# LiBattery-ChargeAndDischarge.net
KiCad netlist of a schematic drawn in Altium Designer
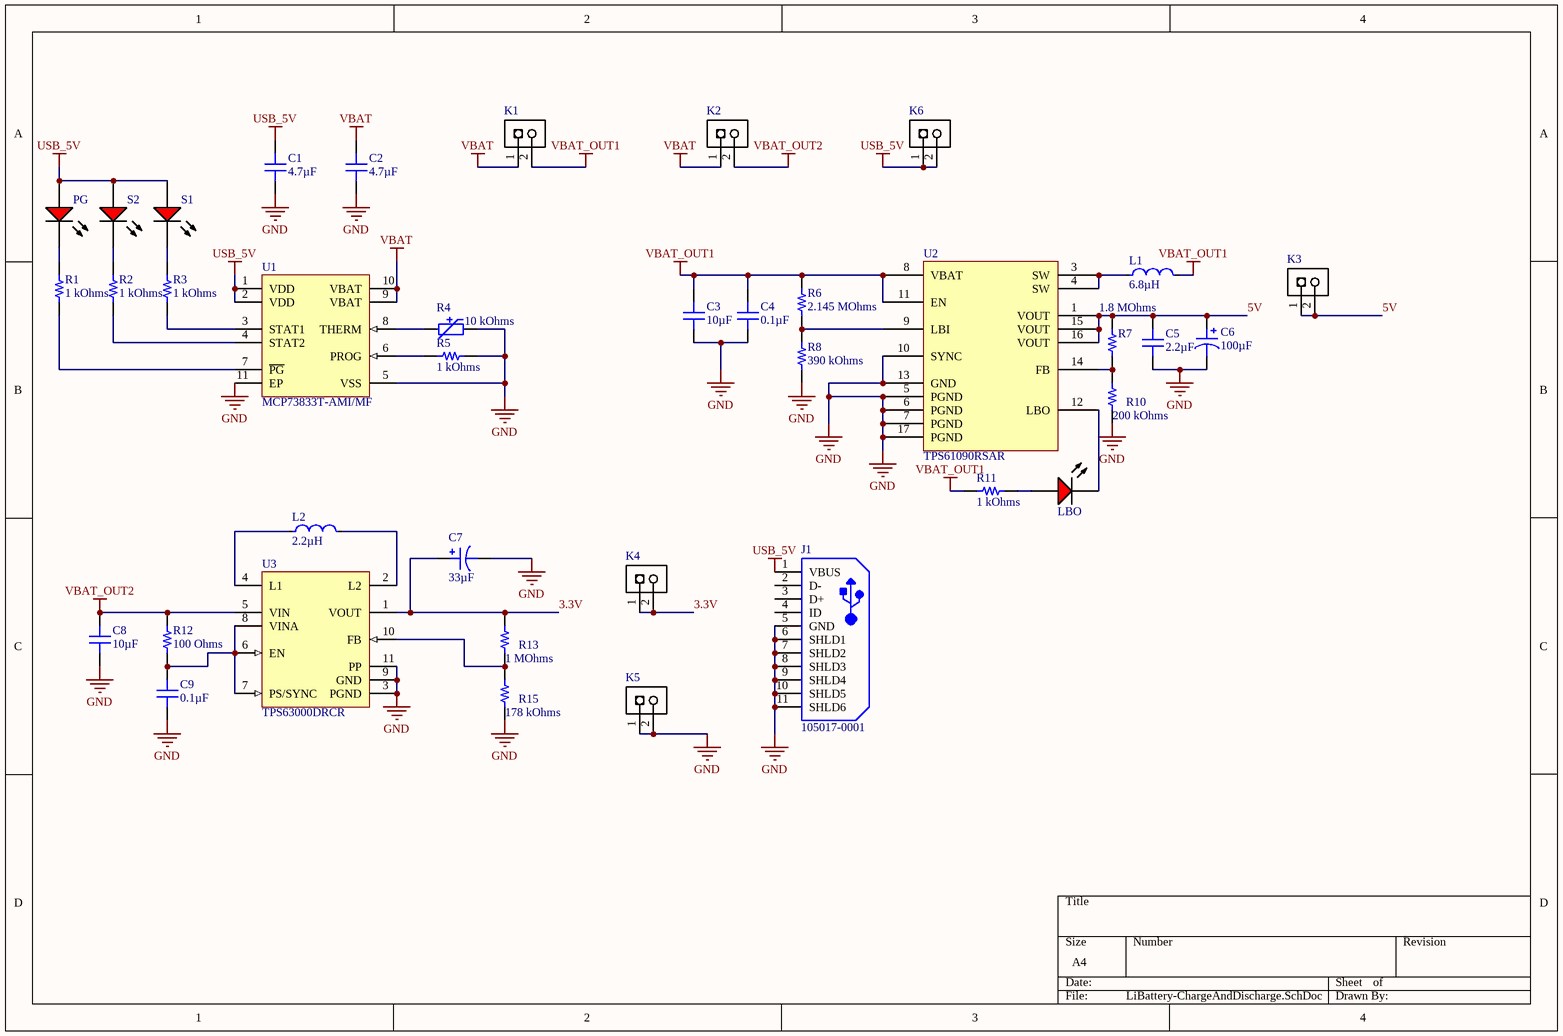
[diagram p0: LiBattery-ChargeAndDischarge.SchDoc]

(export (version "E")
  (design (tool "Eeschema 10.0.6"))
  (components
    (comp (ref "C1")
      (value "4.7µF")
      (footprint "CAP 0603_1608")
      (description "CAP CER 0603 1UF 16V X7R 10%")
      (fields (field (name "PART NUMBER") "C0603C105K4RACAUTO") (field (name "MANUFACTURER") "KEMET"))
      (libsource (lib "Celestial Altium Library - altium_library") (part "Capacitor"))
    )
    (comp (ref "C2")
      (value "4.7µF")
      (footprint "CAP 0603_1608")
      (description "CAP CER 0603 1UF 16V X7R 10%")
      (fields (field (name "PART NUMBER") "C0603C105K4RACAUTO") (field (name "MANUFACTURER") "KEMET"))
      (libsource (lib "Celestial Altium Library - altium_library") (part "Capacitor"))
    )
    (comp (ref "C3")
      (value "10µF")
      (footprint "CAP 0603_1608")
      (description "CAP CER 10UF 6.3V X5R 0603")
      (fields
        (field (name "PART NUMBER") "GRM188R60J106ME47D")
        (field (name "MANUFACTURER") "Murata Electronics")
      )
      (libsource (lib "Celestial Altium Library - altium_library") (part "Capacitor"))
    )
    (comp (ref "C4")
      (value "0.1µF")
      (footprint "CAP 0603_1608")
      (description "CAP CER 0.1UF 10V X7R 0603")
      (fields
        (field (name "PART NUMBER") "100X14W104MV4T")
        (field (name "MANUFACTURER") "Johanson Dielectrics Inc.")
      )
      (libsource (lib "Celestial Altium Library - altium_library") (part "Capacitor"))
    )
    (comp (ref "C5")
      (value "2.2µF")
      (footprint "CAP 0603_1608")
      (description "CAP CER 2.2UF 16V Y5V 0603")
      (fields (field (name "PART NUMBER") "CC0603ZRY5V7BB225") (field (name "MANUFACTURER") "Yageo"))
      (libsource (lib "Celestial Altium Library - altium_library") (part "Capacitor"))
    )
    (comp (ref "C6")
      (value "100µF")
      (footprint "CAP POL 1411_3528")
      (description "CAP TANT 1UF 10% 35V 1411")
      (fields (field (name "PART NUMBER") "CWR11MH105KB") (field (name "MANUFACTURER") "KEMET"))
      (libsource (lib "") (part "Polarised Capacitor_1"))
    )
    (comp (ref "C7")
      (value "33µF")
      (footprint "CAP POL 1411_3528")
      (description "CAP TANT 1UF 10% 35V 1411")
      (fields (field (name "PART NUMBER") "CWR11MH105KB") (field (name "MANUFACTURER") "KEMET"))
      (libsource (lib "Celestial Altium Library - altium_library") (part "Polarised Capacitor"))
    )
    (comp (ref "C8")
      (value "10µF")
      (footprint "CAP 0603_1608")
      (description "CAP CER 10UF 6.3V X5R 0603")
      (fields
        (field (name "PART NUMBER") "GRM188R60J106ME47D")
        (field (name "MANUFACTURER") "Murata Electronics")
      )
      (libsource (lib "Celestial Altium Library - altium_library") (part "Capacitor"))
    )
    (comp (ref "C9")
      (value "0.1µF")
      (footprint "CAP 0603_1608")
      (description "CAP CER 10UF 6.3V X5R 0603")
      (fields
        (field (name "PART NUMBER") "GRM188R60J106ME47D")
        (field (name "MANUFACTURER") "Murata Electronics")
      )
      (libsource (lib "Celestial Altium Library - altium_library") (part "Capacitor"))
    )
    (comp (ref "J1")
      (value "105017-0001")
      (footprint "USB-MICRO-B_V")
      (fields (field (name "MANUFACTURER") "Molex"))
      (libsource (lib "Altium Content Vault") (part "USB-5-6SHLD"))
    )
    (comp (ref "K1")
      (value "HEADER-1X2")
      (footprint "HEADER-1X2")
      (libsource (lib "vh_altium_library") (part "HEADER-1X2"))
    )
    (comp (ref "K2")
      (value "HEADER-1X2")
      (footprint "HEADER-1X2")
      (libsource (lib "vh_altium_library") (part "HEADER-1X2"))
    )
    (comp (ref "K3")
      (value "HEADER-1X2")
      (footprint "HEADER-1X2")
      (libsource (lib "vh_altium_library") (part "HEADER-1X2"))
    )
    (comp (ref "K4")
      (value "HEADER-1X2")
      (footprint "HEADER-1X2")
      (libsource (lib "vh_altium_library") (part "HEADER-1X2"))
    )
    (comp (ref "K5")
      (value "HEADER-1X2")
      (footprint "HEADER-1X2")
      (libsource (lib "vh_altium_library") (part "HEADER-1X2"))
    )
    (comp (ref "K6")
      (value "HEADER-1X2")
      (footprint "HEADER-1X2")
      (libsource (lib "vh_altium_library") (part "HEADER-1X2"))
    )
    (comp (ref "L1")
      (value "6.8µH")
      (footprint "FP-IHLP-2525CZ-FP_2_413x3-MFG")
      (description "Commercial Inductors, High Saturation Series 6.8uH 4.5A 60mΩ 20%")
      (fields (field (name "TOLERANCE") "20%"))
      (libsource (lib "Altium Content Vault") (part "725321dda6339637d4d059423bc1c3c"))
    )
    (comp (ref "L2")
      (value "2.2µH")
      (footprint "FP-IHLP-2525CZ-FP_2_413x3-MFG")
      (description "Commercial Inductors, High Saturation Series 6.8uH 4.5A 60mΩ 20%")
      (fields (field (name "TOLERANCE") "20%"))
      (libsource (lib "Altium Content Vault") (part "725321dda6339637d4d059423bc1c3c"))
    )
    (comp (ref "LBO")
      (value "TLMS1100-GS08")
      (footprint "VISH-TLMX1100_V")
      (description "LED, RED, 2.1 V, -40 to 100 degC, 2-Pin SMD (0603), RoHS, Tape and Reel")
      (fields (field (name "TOLERANCE") "5%"))
      (libsource (lib "Altium Content Vault") (part "LED-RED-AK-2"))
    )
    (comp (ref "PG")
      (value "TLMS1100-GS08")
      (footprint "VISH-TLMX1100_V")
      (description "LED, RED, 2.1 V, -40 to 100 degC, 2-Pin SMD (0603), RoHS, Tape and Reel")
      (fields (field (name "TOLERANCE") "5%"))
      (libsource (lib "Altium Content Vault") (part "LED-RED-AK-2"))
    )
    (comp (ref "R1")
      (value "1 kOhms")
      (footprint "RES 0603_1608")
      (description "RES 10K OHM 0.1% 1/16W 0603")
      (fields
        (field (name "PART NUMBER") "RNCS0603BKE10K0")
        (field (name "MANUFACTURER") "Stackpole Electronics Inc")
      )
      (libsource (lib "Celestial Altium Library - altium_library") (part "Resistor"))
    )
    (comp (ref "R2")
      (value "1 kOhms")
      (footprint "RES 0603_1608")
      (description "RES 10K OHM 0.1% 1/16W 0603")
      (fields
        (field (name "PART NUMBER") "RNCS0603BKE10K0")
        (field (name "MANUFACTURER") "Stackpole Electronics Inc")
      )
      (libsource (lib "Celestial Altium Library - altium_library") (part "Resistor"))
    )
    (comp (ref "R3")
      (value "1 kOhms")
      (footprint "RES 0603_1608")
      (description "RES 10K OHM 0.1% 1/16W 0603")
      (fields
        (field (name "PART NUMBER") "RNCS0603BKE10K0")
        (field (name "MANUFACTURER") "Stackpole Electronics Inc")
      )
      (libsource (lib "Celestial Altium Library - altium_library") (part "Resistor"))
    )
    (comp (ref "R4")
      (value "10 kOhms")
      (footprint "PTC 0603_1608")
      (description "THERMISTOR PTC 470 OHM 50% 0603")
      (fields
        (field (name "PART NUMBER") "B59641A0145A062")
        (field (name "MANUFACTURER") "TDK Electronics Inc.")
      )
      (libsource (lib "Celestial Altium Library - altium_library") (part "Thermistor PTC"))
    )
    (comp (ref "R5")
      (value "1 kOhms")
      (footprint "RES 0603_1608")
      (description "RES 10K OHM 0.1% 1/16W 0603")
      (fields
        (field (name "PART NUMBER") "RNCS0603BKE10K0")
        (field (name "MANUFACTURER") "Stackpole Electronics Inc")
      )
      (libsource (lib "Celestial Altium Library - altium_library") (part "Resistor"))
    )
    (comp (ref "R6")
      (value "2.145 MOhms")
      (footprint "RES 0603_1608")
      (description "RES 2.32M OHM 1% 1/10W 0603")
      (fields
        (field (name "PART NUMBER") "RMCF0603FT2M32")
        (field (name "MANUFACTURER") "Stackpole Electronics Inc")
      )
      (libsource (lib "Celestial Altium Library - altium_library") (part "Resistor"))
    )
    (comp (ref "R7")
      (value "1.8 MOhms")
      (footprint "RES 0603_1608")
      (description "RES 10K OHM 0.1% 1/16W 0603")
      (fields
        (field (name "PART NUMBER") "RNCS0603BKE10K0")
        (field (name "MANUFACTURER") "Stackpole Electronics Inc")
      )
      (libsource (lib "Celestial Altium Library - altium_library") (part "Resistor"))
    )
    (comp (ref "R8")
      (value "390 kOhms")
      (footprint "RES 0603_1608")
      (description "CRGP 0603 390K 1%")
      (fields
        (field (name "PART NUMBER") "CRGP0603F390K")
        (field (name "MANUFACTURER") "TE Connectivity Passive Product")
      )
      (libsource (lib "Celestial Altium Library - altium_library") (part "Resistor"))
    )
    (comp (ref "R10")
      (value "200 kOhms")
      (footprint "RES 0603_1608")
      (description "RES 10K OHM 0.1% 1/16W 0603")
      (fields
        (field (name "PART NUMBER") "RNCS0603BKE10K0")
        (field (name "MANUFACTURER") "Stackpole Electronics Inc")
      )
      (libsource (lib "Celestial Altium Library - altium_library") (part "Resistor"))
    )
    (comp (ref "R11")
      (value "1 kOhms")
      (footprint "RES 0603_1608")
      (description "RES 10K OHM 0.1% 1/16W 0603")
      (fields
        (field (name "PART NUMBER") "RNCS0603BKE10K0")
        (field (name "MANUFACTURER") "Stackpole Electronics Inc")
      )
      (libsource (lib "Celestial Altium Library - altium_library") (part "Resistor"))
    )
    (comp (ref "R12")
      (value "100 Ohms")
      (footprint "RES 0603_1608")
      (description "RES 10K OHM 0.1% 1/16W 0603")
      (fields
        (field (name "PART NUMBER") "RNCS0603BKE10K0")
        (field (name "MANUFACTURER") "Stackpole Electronics Inc")
      )
      (libsource (lib "Celestial Altium Library - altium_library") (part "Resistor"))
    )
    (comp (ref "R13")
      (value "1 MOhms")
      (footprint "RES 0603_1608")
      (description "RES 10K OHM 0.1% 1/16W 0603")
      (fields
        (field (name "PART NUMBER") "RNCS0603BKE10K0")
        (field (name "MANUFACTURER") "Stackpole Electronics Inc")
      )
      (libsource (lib "Celestial Altium Library - altium_library") (part "Resistor"))
    )
    (comp (ref "R15")
      (value "178 kOhms")
      (footprint "RES 0603_1608")
      (description "RES 10K OHM 0.1% 1/16W 0603")
      (fields
        (field (name "PART NUMBER") "RNCS0603BKE10K0")
        (field (name "MANUFACTURER") "Stackpole Electronics Inc")
      )
      (libsource (lib "Celestial Altium Library - altium_library") (part "Resistor"))
    )
    (comp (ref "S1")
      (value "TLMS1100-GS08")
      (footprint "VISH-TLMX1100_V")
      (description "LED, RED, 2.1 V, -40 to 100 degC, 2-Pin SMD (0603), RoHS, Tape and Reel")
      (fields (field (name "TOLERANCE") "5%"))
      (libsource (lib "Altium Content Vault") (part "LED-RED-AK-2"))
    )
    (comp (ref "S2")
      (value "TLMS1100-GS08")
      (footprint "VISH-TLMX1100_V")
      (description "LED, RED, 2.1 V, -40 to 100 degC, 2-Pin SMD (0603), RoHS, Tape and Reel")
      (fields (field (name "TOLERANCE") "5%"))
      (libsource (lib "Altium Content Vault") (part "LED-RED-AK-2"))
    )
    (comp (ref "U1")
      (value "MCP73833T-AMI/MF")
      (footprint "DFN-MF10")
      (libsource (lib "Altium Content Vault") (part "PM-BM-MCP73833-IL11"))
    )
    (comp (ref "U2")
      (value "TPS61090RSAR")
      (footprint "TI VQFN-16 4X4MM RSA")
      (description "IC REG BOOST ADJUSTABLE 2A 16QFN")
      (fields (field (name "MANUFACTURER") "Texas Instruments"))
      (libsource (lib "Celestial Altium Library - altium_library") (part "TI TPS61090/1/2"))
    )
    (comp (ref "U3")
      (value "TPS63000DRCR")
      (footprint "DRC0010J_V")
      (fields (field (name "MANUFACTURER") "Texas Instruments"))
      (libsource (lib "Altium Content Vault") (part "TI-TPS63000DRC10-3000X1650TP"))
    )
  )
  (nets
    (net (code "1") (name "/3.3V") (class "Default")
      (node (ref "C7") (pin "1") (pinfunction "1_1") (pintype "passive"))
      (node (ref "K4") (pin "1") (pintype "passive"))
      (node (ref "K4") (pin "2") (pintype "passive"))
      (node (ref "R13") (pin "1") (pinfunction "1_1") (pintype "passive"))
      (node (ref "U3") (pin "1") (pinfunction "VOUT_1") (pintype "power_in"))
    )
    (net (code "2") (name "/5V") (class "Default")
      (node (ref "C5") (pin "2") (pinfunction "2_2") (pintype "passive"))
      (node (ref "C6") (pin "1") (pinfunction "1_1") (pintype "passive"))
      (node (ref "K3") (pin "1") (pintype "passive"))
      (node (ref "K3") (pin "2") (pintype "passive"))
      (node (ref "R7") (pin "1") (pinfunction "1_1") (pintype "passive"))
      (node (ref "U2") (pin "1") (pinfunction "VOUT_1") (pintype "passive"))
      (node (ref "U2") (pin "15") (pinfunction "VOUT_15") (pintype "passive"))
      (node (ref "U2") (pin "16") (pinfunction "VOUT_16") (pintype "passive"))
    )
    (net (code "3") (name "GND") (class "Default")
      (node (ref "C1") (pin "1") (pinfunction "1_1") (pintype "passive"))
      (node (ref "C2") (pin "1") (pinfunction "1_1") (pintype "passive"))
      (node (ref "C3") (pin "1") (pinfunction "1_1") (pintype "passive"))
      (node (ref "C4") (pin "2") (pinfunction "2_2") (pintype "passive"))
      (node (ref "C5") (pin "1") (pinfunction "1_1") (pintype "passive"))
      (node (ref "C6") (pin "2") (pinfunction "2_2") (pintype "passive"))
      (node (ref "C7") (pin "2") (pinfunction "2_2") (pintype "passive"))
      (node (ref "C8") (pin "1") (pinfunction "1_1") (pintype "passive"))
      (node (ref "C9") (pin "2") (pinfunction "2_2") (pintype "passive"))
      (node (ref "J1") (pin "10") (pinfunction "SHLD5_10") (pintype "passive"))
      (node (ref "J1") (pin "11") (pinfunction "SHLD6_11") (pintype "passive"))
      (node (ref "J1") (pin "5") (pinfunction "GND_5") (pintype "passive"))
      (node (ref "J1") (pin "6") (pinfunction "SHLD1_6") (pintype "passive"))
      (node (ref "J1") (pin "7") (pinfunction "SHLD2_7") (pintype "passive"))
      (node (ref "J1") (pin "8") (pinfunction "SHLD3_8") (pintype "passive"))
      (node (ref "J1") (pin "9") (pinfunction "SHLD4_9") (pintype "passive"))
      (node (ref "K5") (pin "1") (pintype "passive"))
      (node (ref "K5") (pin "2") (pintype "passive"))
      (node (ref "R10") (pin "2") (pinfunction "2_2") (pintype "passive"))
      (node (ref "R15") (pin "2") (pinfunction "2_2") (pintype "passive"))
      (node (ref "R4") (pin "1") (pinfunction "1_1") (pintype "passive"))
      (node (ref "R5") (pin "1") (pinfunction "1_1") (pintype "passive"))
      (node (ref "R8") (pin "1") (pinfunction "1_1") (pintype "passive"))
      (node (ref "U1") (pin "11") (pinfunction "EP_11") (pintype "power_in"))
      (node (ref "U1") (pin "5") (pinfunction "VSS_5") (pintype "power_in"))
      (node (ref "U2") (pin "10") (pinfunction "SYNC_10") (pintype "passive"))
      (node (ref "U2") (pin "13") (pinfunction "GND_13") (pintype "passive"))
      (node (ref "U2") (pin "17") (pinfunction "PGND_17") (pintype "passive"))
      (node (ref "U2") (pin "5") (pinfunction "PGND_5") (pintype "passive"))
      (node (ref "U2") (pin "6") (pinfunction "PGND_6") (pintype "passive"))
      (node (ref "U2") (pin "7") (pinfunction "PGND_7") (pintype "passive"))
      (node (ref "U3") (pin "11") (pinfunction "PP_11") (pintype "power_in"))
      (node (ref "U3") (pin "3") (pinfunction "PGND_3") (pintype "power_in"))
      (node (ref "U3") (pin "9") (pinfunction "GND_9") (pintype "power_in"))
    )
    (net (code "4") (name "Net-(L1-Pad1)") (class "Default")
      (node (ref "L1") (pin "1") (pinfunction "1_1") (pintype "passive"))
      (node (ref "U2") (pin "3") (pinfunction "SW_3") (pintype "passive"))
      (node (ref "U2") (pin "4") (pinfunction "SW_4") (pintype "passive"))
    )
    (net (code "5") (name "Net-(LBO-A)") (class "Default")
      (node (ref "LBO") (pin "1") (pinfunction "A_1") (pintype "passive"))
      (node (ref "R11") (pin "1") (pinfunction "1_1") (pintype "passive"))
    )
    (net (code "6") (name "Net-(LBO-K)") (class "Default")
      (node (ref "LBO") (pin "2") (pinfunction "K_2") (pintype "passive"))
      (node (ref "U2") (pin "12") (pinfunction "LBO_12") (pintype "passive"))
    )
    (net (code "7") (name "Net-(PG-K)") (class "Default")
      (node (ref "PG") (pin "2") (pinfunction "K_2") (pintype "passive"))
      (node (ref "R1") (pin "2") (pinfunction "2_2") (pintype "passive"))
    )
    (net (code "8") (name "Net-(S1-K)") (class "Default")
      (node (ref "R3") (pin "2") (pinfunction "2_2") (pintype "passive"))
      (node (ref "S1") (pin "2") (pinfunction "K_2") (pintype "passive"))
    )
    (net (code "9") (name "Net-(S2-K)") (class "Default")
      (node (ref "R2") (pin "2") (pinfunction "2_2") (pintype "passive"))
      (node (ref "S2") (pin "2") (pinfunction "K_2") (pintype "passive"))
    )
    (net (code "10") (name "Net-(U1-PROG)") (class "Default")
      (node (ref "R5") (pin "2") (pinfunction "2_2") (pintype "passive"))
      (node (ref "U1") (pin "6") (pinfunction "PROG_6") (pintype "input"))
    )
    (net (code "11") (name "Net-(U1-STAT1)") (class "Default")
      (node (ref "R3") (pin "1") (pinfunction "1_1") (pintype "passive"))
      (node (ref "U1") (pin "3") (pinfunction "STAT1_3") (pintype "open_collector"))
    )
    (net (code "12") (name "Net-(U1-STAT2)") (class "Default")
      (node (ref "R2") (pin "1") (pinfunction "1_1") (pintype "passive"))
      (node (ref "U1") (pin "4") (pinfunction "STAT2_4") (pintype "open_collector"))
    )
    (net (code "13") (name "Net-(U1-THERM)") (class "Default")
      (node (ref "R4") (pin "2") (pinfunction "2_2") (pintype "passive"))
      (node (ref "U1") (pin "8") (pinfunction "THERM_8") (pintype "input"))
    )
    (net (code "14") (name "Net-(U1-~{PG})") (class "Default")
      (node (ref "R1") (pin "1") (pinfunction "1_1") (pintype "passive"))
      (node (ref "U1") (pin "7") (pinfunction "~{PG}_7") (pintype "open_collector"))
    )
    (net (code "15") (name "Net-(U2-FB)") (class "Default")
      (node (ref "R10") (pin "1") (pinfunction "1_1") (pintype "passive"))
      (node (ref "R7") (pin "2") (pinfunction "2_2") (pintype "passive"))
      (node (ref "U2") (pin "14") (pinfunction "FB_14") (pintype "passive"))
    )
    (net (code "16") (name "Net-(U2-LBI)") (class "Default")
      (node (ref "R6") (pin "1") (pinfunction "1_1") (pintype "passive"))
      (node (ref "R8") (pin "2") (pinfunction "2_2") (pintype "passive"))
      (node (ref "U2") (pin "9") (pinfunction "LBI_9") (pintype "passive"))
    )
    (net (code "17") (name "Net-(U3-EN)") (class "Default")
      (node (ref "C9") (pin "1") (pinfunction "1_1") (pintype "passive"))
      (node (ref "R12") (pin "2") (pinfunction "2_2") (pintype "passive"))
      (node (ref "U3") (pin "6") (pinfunction "EN_6") (pintype "input"))
      (node (ref "U3") (pin "7") (pinfunction "PS/SYNC_7") (pintype "input"))
      (node (ref "U3") (pin "8") (pinfunction "VINA_8") (pintype "power_in"))
    )
    (net (code "18") (name "Net-(U3-FB)") (class "Default")
      (node (ref "R13") (pin "2") (pinfunction "2_2") (pintype "passive"))
      (node (ref "R15") (pin "1") (pinfunction "1_1") (pintype "passive"))
      (node (ref "U3") (pin "10") (pinfunction "FB_10") (pintype "input"))
    )
    (net (code "19") (name "Net-(U3-L1)") (class "Default")
      (node (ref "L2") (pin "1") (pinfunction "1_1") (pintype "passive"))
      (node (ref "U3") (pin "4") (pinfunction "L1_4") (pintype "passive"))
    )
    (net (code "20") (name "Net-(U3-L2)") (class "Default")
      (node (ref "L2") (pin "2") (pinfunction "2_2") (pintype "passive"))
      (node (ref "U3") (pin "2") (pinfunction "L2_2") (pintype "passive"))
    )
    (net (code "21") (name "USB_5V") (class "Default")
      (node (ref "C1") (pin "2") (pinfunction "2_2") (pintype "passive"))
      (node (ref "J1") (pin "1") (pinfunction "VBUS_1") (pintype "passive"))
      (node (ref "K6") (pin "1") (pintype "passive"))
      (node (ref "K6") (pin "2") (pintype "passive"))
      (node (ref "PG") (pin "1") (pinfunction "A_1") (pintype "passive"))
      (node (ref "S1") (pin "1") (pinfunction "A_1") (pintype "passive"))
      (node (ref "S2") (pin "1") (pinfunction "A_1") (pintype "passive"))
      (node (ref "U1") (pin "1") (pinfunction "VDD_1") (pintype "power_in"))
      (node (ref "U1") (pin "2") (pinfunction "VDD_2") (pintype "power_in"))
    )
    (net (code "22") (name "VBAT") (class "Default")
      (node (ref "C2") (pin "2") (pinfunction "2_2") (pintype "passive"))
      (node (ref "K1") (pin "1") (pintype "passive"))
      (node (ref "K2") (pin "1") (pintype "passive"))
      (node (ref "U1") (pin "10") (pinfunction "VBAT_10") (pintype "power_in"))
      (node (ref "U1") (pin "9") (pinfunction "VBAT_9") (pintype "power_in"))
    )
    (net (code "23") (name "VBAT_OUT1") (class "Default")
      (node (ref "C3") (pin "2") (pinfunction "2_2") (pintype "passive"))
      (node (ref "C4") (pin "1") (pinfunction "1_1") (pintype "passive"))
      (node (ref "K1") (pin "2") (pintype "passive"))
      (node (ref "L1") (pin "2") (pinfunction "2_2") (pintype "passive"))
      (node (ref "R11") (pin "2") (pinfunction "2_2") (pintype "passive"))
      (node (ref "R6") (pin "2") (pinfunction "2_2") (pintype "passive"))
      (node (ref "U2") (pin "11") (pinfunction "EN_11") (pintype "passive"))
      (node (ref "U2") (pin "8") (pinfunction "VBAT_8") (pintype "passive"))
    )
    (net (code "24") (name "VBAT_OUT2") (class "Default")
      (node (ref "C8") (pin "2") (pinfunction "2_2") (pintype "passive"))
      (node (ref "K2") (pin "2") (pintype "passive"))
      (node (ref "R12") (pin "1") (pinfunction "1_1") (pintype "passive"))
      (node (ref "U3") (pin "5") (pinfunction "VIN_5") (pintype "power_in"))
    )
    (net (code "25") (name "unconnected-(J1-D+-Pad3)") (class "Default")
      (node (ref "J1") (pin "3") (pinfunction "D+_3") (pintype "passive"))
    )
    (net (code "26") (name "unconnected-(J1-D--Pad2)") (class "Default")
      (node (ref "J1") (pin "2") (pinfunction "D-_2") (pintype "passive"))
    )
    (net (code "27") (name "unconnected-(J1-ID-Pad4)") (class "Default")
      (node (ref "J1") (pin "4") (pinfunction "ID_4") (pintype "passive"))
    )
  )
)
